# dengenver2_0.net
KiCad netlist of a schematic drawn in EAGLE
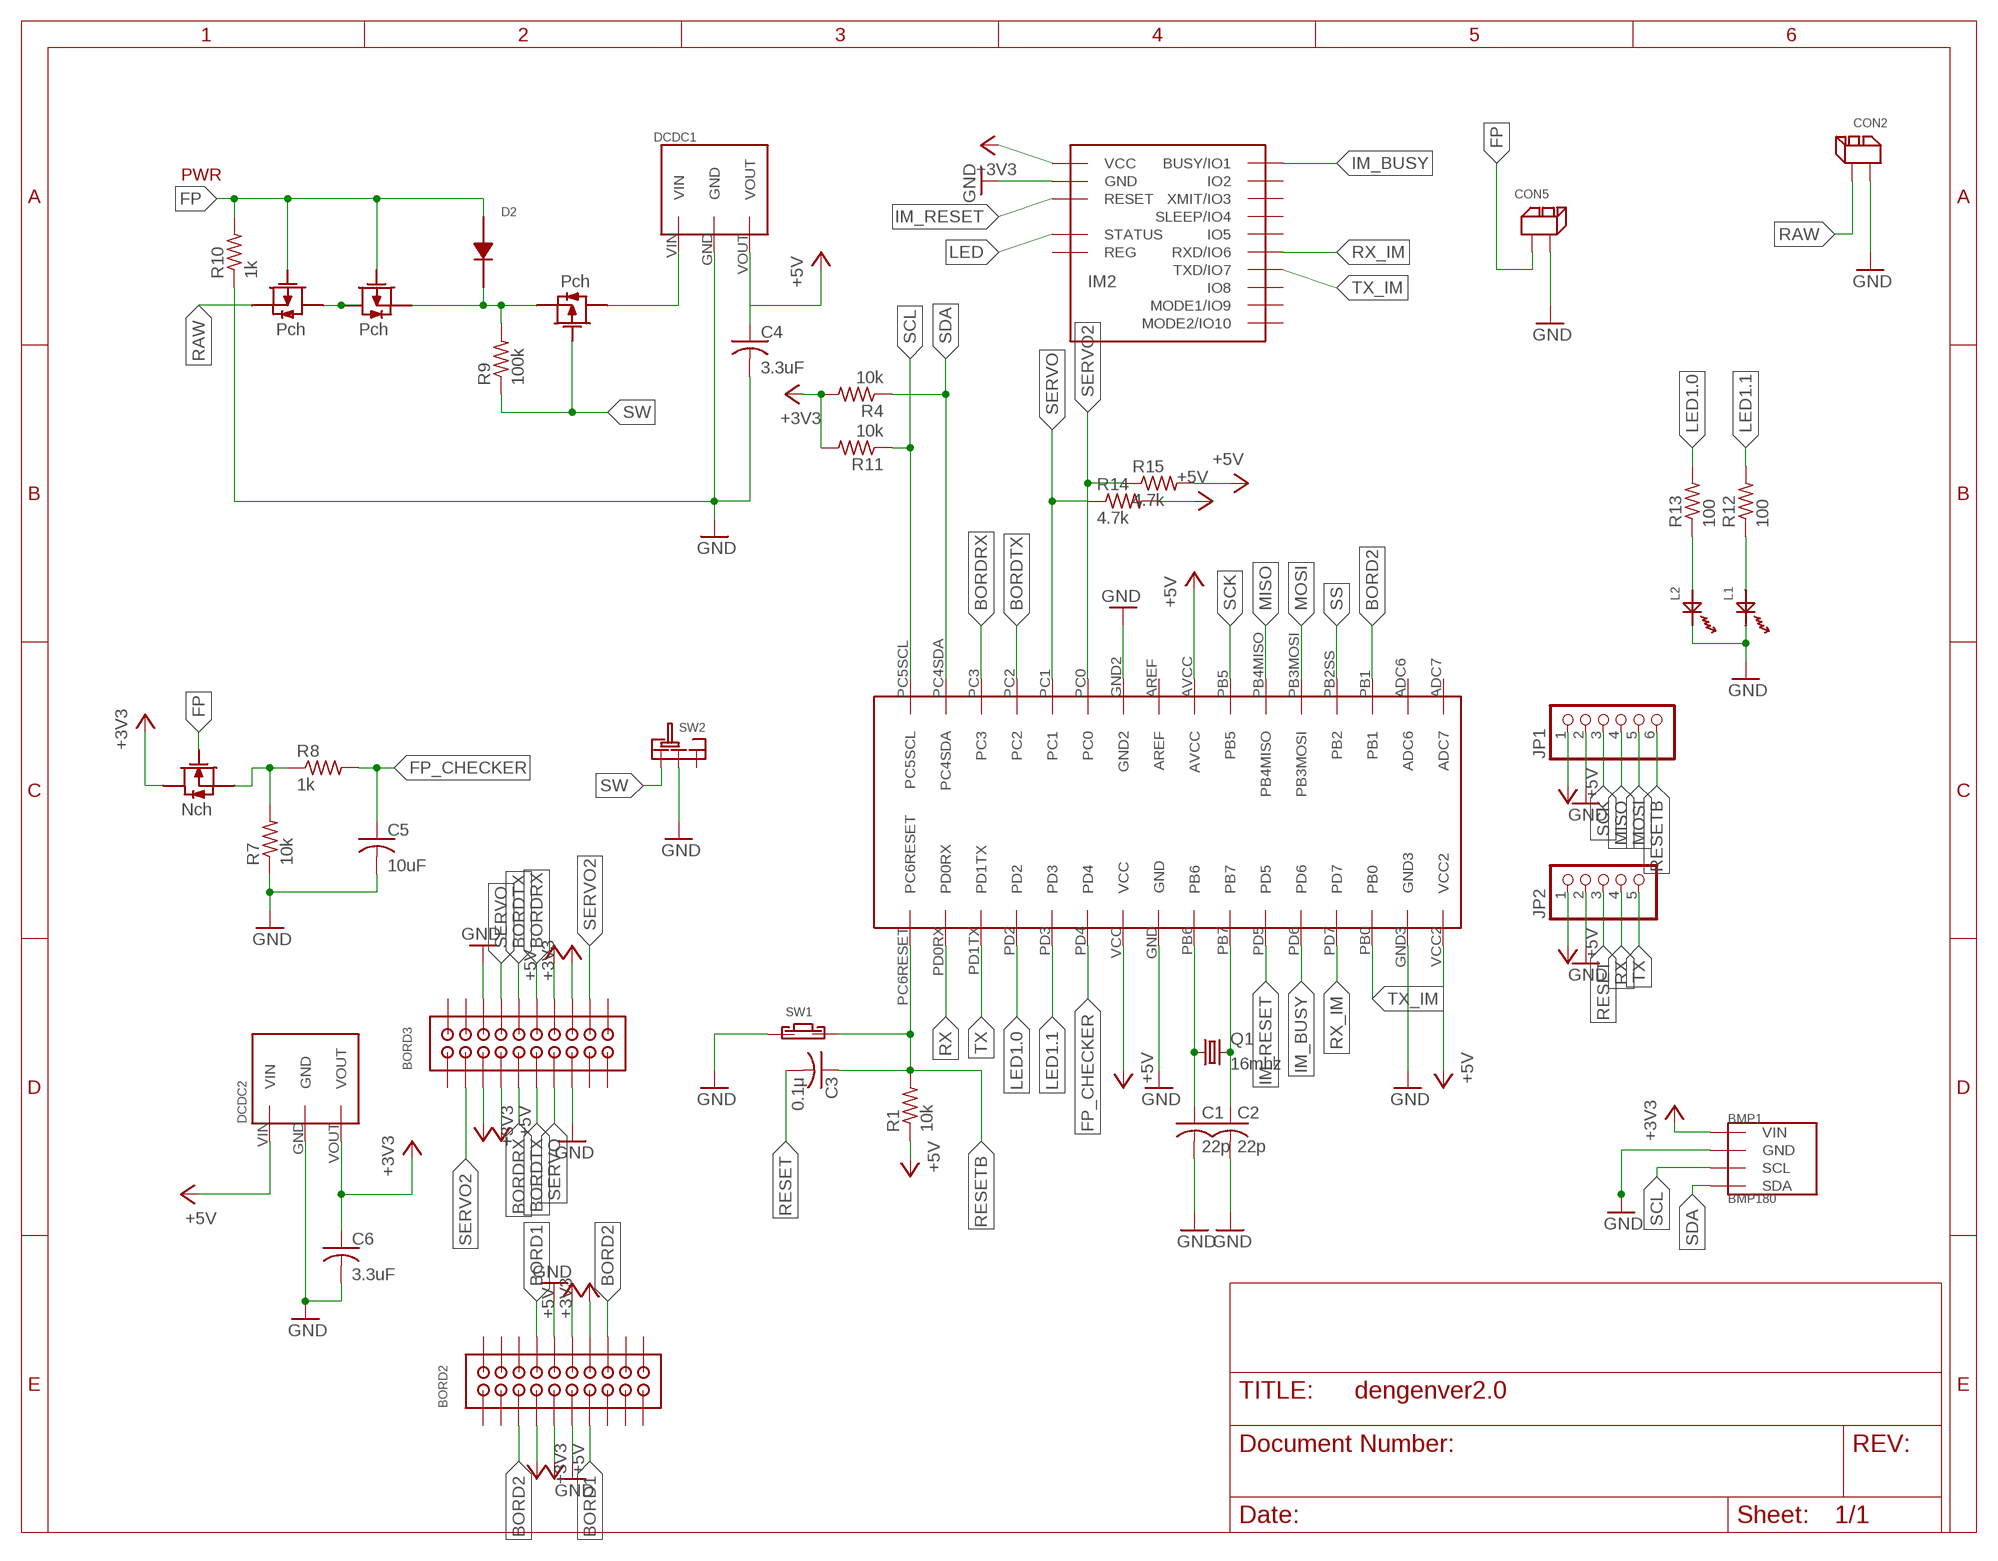
[diagram p0: schematic, sheet 1]

(export (version "E")
  (design (tool "Eeschema 10.0.6"))
  (components
    (comp (ref "BMP1")
      (value "BMP180")
      (footprint "eagle-import:GY-68")
      (libsource (lib "eagle-import") (part "BMP180"))
    )
    (comp (ref "BORD2")
      (value "2X10")
      (footprint "eagle-import:2X10")
      (libsource (lib "eagle-import") (part "2X10"))
    )
    (comp (ref "BORD3")
      (value "2X10")
      (footprint "eagle-import:2X10")
      (libsource (lib "eagle-import") (part "2X10"))
    )
    (comp (ref "C1")
      (value "22p")
      (footprint "eagle-import:C1608")
      (libsource (lib "eagle-import") (part "C-USC1608"))
    )
    (comp (ref "C2")
      (value "22p")
      (footprint "eagle-import:C1608")
      (libsource (lib "eagle-import") (part "C-USC1608"))
    )
    (comp (ref "C3")
      (value "0.1μ")
      (footprint "eagle-import:C1608")
      (libsource (lib "eagle-import") (part "C-USC1608"))
    )
    (comp (ref "C4")
      (value "3.3uF")
      (footprint "eagle-import:C1608")
      (libsource (lib "eagle-import") (part "C-USC1608"))
    )
    (comp (ref "C5")
      (value "10uF")
      (footprint "eagle-import:C1608")
      (libsource (lib "eagle-import") (part "C-USC1608"))
    )
    (comp (ref "C6")
      (value "3.3uF")
      (footprint "eagle-import:C1608")
      (libsource (lib "eagle-import") (part "C-USC1608"))
    )
    (comp (ref "CON2")
      (value "2PIN")
      (footprint "eagle-import:2PIN")
      (libsource (lib "eagle-import") (part "2PIN"))
    )
    (comp (ref "CON5")
      (value "2PIN")
      (footprint "eagle-import:2PIN")
      (libsource (lib "eagle-import") (part "2PIN"))
    )
    (comp (ref "D2")
      (value "1W4148W")
      (footprint "eagle-import:SOD-123")
      (libsource (lib "eagle-import") (part "1W4148W"))
    )
    (comp (ref "DCDC1")
      (value "5V1A_M78AR05-1")
      (footprint "eagle-import:5V1A_M78AR05-1")
      (libsource (lib "eagle-import") (part "5V1A_M78AR05-1"))
    )
    (comp (ref "DCDC2")
      (value "3.3V1A_M78AR033-1")
      (footprint "eagle-import:3.3V1A_M78AR033-1")
      (libsource (lib "eagle-import") (part "3.3V1A_M78AR033-1"))
    )
    (comp (ref "IM2")
      (value "IM920_IM920C")
      (footprint "eagle-import:IM920_IM920C")
      (libsource (lib "eagle-import") (part "IM920_IM920C"))
    )
    (comp (ref "JP1")
      (value "PINHD-1X6")
      (footprint "eagle-import:1X06")
      (libsource (lib "eagle-import") (part "PINHD-1X6"))
    )
    (comp (ref "JP2")
      (value "PINHD-1X5")
      (footprint "eagle-import:1X05")
      (libsource (lib "eagle-import") (part "PINHD-1X5"))
    )
    (comp (ref "L1")
      (value "OSXX1608C1A")
      (footprint "eagle-import:OSXX1608C1A")
      (libsource (lib "eagle-import") (part "OSXX1608C1A"))
    )
    (comp (ref "L2")
      (value "OSXX1608C1A")
      (footprint "eagle-import:OSXX1608C1A")
      (libsource (lib "eagle-import") (part "OSXX1608C1A"))
    )
    (comp (ref "Q1")
      (value "16mhz")
      (footprint "eagle-import:HC49UP")
      (libsource (lib "eagle-import") (part "CRYSTALHC49UP"))
    )
    (comp (ref "R1")
      (value "10k")
      (footprint "eagle-import:R0603")
      (libsource (lib "eagle-import") (part "R-US_R0603"))
    )
    (comp (ref "R4")
      (value "10k")
      (footprint "eagle-import:R0603")
      (libsource (lib "eagle-import") (part "R-US_R0603"))
    )
    (comp (ref "R7")
      (value "10k")
      (footprint "eagle-import:R0603")
      (libsource (lib "eagle-import") (part "R-US_R0603"))
    )
    (comp (ref "R8")
      (value "1k")
      (footprint "eagle-import:R0603")
      (libsource (lib "eagle-import") (part "R-US_R0603"))
    )
    (comp (ref "R9")
      (value "100k")
      (footprint "eagle-import:R0603")
      (libsource (lib "eagle-import") (part "R-US_R0603"))
    )
    (comp (ref "R10")
      (value "1k")
      (footprint "eagle-import:R0603")
      (libsource (lib "eagle-import") (part "R-US_R0603"))
    )
    (comp (ref "R11")
      (value "10k")
      (footprint "eagle-import:R0603")
      (libsource (lib "eagle-import") (part "R-US_R0603"))
    )
    (comp (ref "R12")
      (value "100")
      (footprint "eagle-import:R0603")
      (libsource (lib "eagle-import") (part "R-US_R0603"))
    )
    (comp (ref "R13")
      (value "100")
      (footprint "eagle-import:R0603")
      (libsource (lib "eagle-import") (part "R-US_R0603"))
    )
    (comp (ref "R14")
      (value "4.7k")
      (footprint "eagle-import:R0603")
      (libsource (lib "eagle-import") (part "R-US_R0603"))
    )
    (comp (ref "R15")
      (value "4.7k")
      (footprint "eagle-import:R0603")
      (libsource (lib "eagle-import") (part "R-US_R0603"))
    )
    (comp (ref "SW1")
      (value "TVAF06-A020B-R")
      (footprint "eagle-import:TVAF06-A020B-R")
      (libsource (lib "eagle-import") (part "TVAF06-A020B-R"))
    )
    (comp (ref "SW2")
      (value "SRIDE_SWITCH")
      (footprint "eagle-import:SRIDE_SWITCH")
      (libsource (lib "eagle-import") (part "SRIDE_SWITCH"))
    )
    (comp (ref "U$1")
      (value "ATMEGA328P-AU")
      (footprint "eagle-import:QFP80P900X900X120-32N")
      (libsource (lib "eagle-import") (part "ATMEGA328P-AU"))
    )
    (comp (ref "U$2")
      (value "2SJ681-PCH")
      (footprint "eagle-import:2SJ681")
      (libsource (lib "eagle-import") (part "2SJ681-PCH"))
    )
    (comp (ref "U$3")
      (value "2SK4017-NCH")
      (footprint "eagle-import:2SK4017")
      (libsource (lib "eagle-import") (part "2SK4017-NCH"))
    )
    (comp (ref "U$4")
      (value "2SJ681-PCH")
      (footprint "eagle-import:2SJ681")
      (libsource (lib "eagle-import") (part "2SJ681-PCH"))
    )
    (comp (ref "U$5")
      (value "2SJ681-PCH")
      (footprint "eagle-import:2SJ681")
      (libsource (lib "eagle-import") (part "2SJ681-PCH"))
    )
  )
  (nets
    (net (code "1") (name "+3V3") (class "Default")
      (node (ref "BMP1") (pin "P1") (pinfunction "VIN_P1") (pintype "bidirectional"))
      (node (ref "BORD2") (pin "P$14") (pinfunction "P$14_P$14") (pintype "bidirectional"))
      (node (ref "BORD2") (pin "P$7") (pinfunction "P$7_P$7") (pintype "bidirectional"))
      (node (ref "BORD3") (pin "P$16") (pinfunction "P$16_P$16") (pintype "bidirectional"))
      (node (ref "BORD3") (pin "P$5") (pinfunction "P$5_P$5") (pintype "bidirectional"))
      (node (ref "C6") (pin "1") (pinfunction "1_1") (pintype "passive"))
      (node (ref "DCDC2") (pin "VOUT") (pinfunction "VOUT_VOUT") (pintype "bidirectional"))
      (node (ref "IM2") (pin "$P17") (pinfunction "VCC_$P17") (pintype "bidirectional"))
      (node (ref "R11") (pin "2") (pinfunction "2_2") (pintype "passive"))
      (node (ref "R4") (pin "2") (pinfunction "2_2") (pintype "passive"))
      (node (ref "U$3") (pin "DRAIN") (pinfunction "DRAIN_DRAIN") (pintype "bidirectional"))
    )
    (net (code "2") (name "+5V") (class "Default")
      (node (ref "BORD2") (pin "P$12") (pinfunction "P$12_P$12") (pintype "bidirectional"))
      (node (ref "BORD2") (pin "P$9") (pinfunction "P$9_P$9") (pintype "bidirectional"))
      (node (ref "BORD3") (pin "P$14") (pinfunction "P$14_P$14") (pintype "bidirectional"))
      (node (ref "BORD3") (pin "P$7") (pinfunction "P$7_P$7") (pintype "bidirectional"))
      (node (ref "C4") (pin "1") (pinfunction "1_1") (pintype "passive"))
      (node (ref "DCDC1") (pin "VOUT") (pinfunction "VOUT_VOUT") (pintype "bidirectional"))
      (node (ref "DCDC2") (pin "VIN") (pinfunction "VIN_VIN") (pintype "bidirectional"))
      (node (ref "JP1") (pin "1") (pinfunction "1_1") (pintype "passive"))
      (node (ref "JP2") (pin "1") (pinfunction "1_1") (pintype "passive"))
      (node (ref "R1") (pin "1") (pinfunction "1_1") (pintype "passive"))
      (node (ref "R14") (pin "2") (pinfunction "2_2") (pintype "passive"))
      (node (ref "R15") (pin "2") (pinfunction "2_2") (pintype "passive"))
      (node (ref "U$1") (pin "AVCC") (pinfunction "AVCC_AVCC") (pintype "bidirectional"))
      (node (ref "U$1") (pin "VCC") (pinfunction "VCC_VCC") (pintype "bidirectional"))
      (node (ref "U$1") (pin "VCC2") (pinfunction "VCC2_VCC2") (pintype "bidirectional"))
    )
    (net (code "3") (name "BORD1") (class "Default")
      (node (ref "BORD2") (pin "P$13") (pinfunction "P$13_P$13") (pintype "bidirectional"))
      (node (ref "BORD2") (pin "P$8") (pinfunction "P$8_P$8") (pintype "bidirectional"))
    )
    (net (code "4") (name "BORD2") (class "Default")
      (node (ref "BORD2") (pin "P$16") (pinfunction "P$16_P$16") (pintype "bidirectional"))
      (node (ref "BORD2") (pin "P$5") (pinfunction "P$5_P$5") (pintype "bidirectional"))
      (node (ref "U$1") (pin "PB1") (pinfunction "PB1_PB1") (pintype "bidirectional"))
    )
    (net (code "5") (name "BORDRX") (class "Default")
      (node (ref "BORD3") (pin "P$12") (pinfunction "P$12_P$12") (pintype "bidirectional"))
      (node (ref "BORD3") (pin "P$9") (pinfunction "P$9_P$9") (pintype "bidirectional"))
      (node (ref "U$1") (pin "PC3") (pinfunction "PC3_PC3") (pintype "bidirectional"))
    )
    (net (code "6") (name "BORDTX") (class "Default")
      (node (ref "BORD3") (pin "P$10") (pinfunction "P$10_P$10") (pintype "bidirectional"))
      (node (ref "BORD3") (pin "P$11") (pinfunction "P$11_P$11") (pintype "bidirectional"))
      (node (ref "U$1") (pin "PC2") (pinfunction "PC2_PC2") (pintype "bidirectional"))
    )
    (net (code "7") (name "FP") (class "Default")
      (node (ref "CON5") (pin "P$1") (pinfunction "P$1_P$1") (pintype "bidirectional"))
      (node (ref "D2") (pin "C") (pinfunction "C_C") (pintype "bidirectional"))
      (node (ref "R10") (pin "2") (pinfunction "2_2") (pintype "passive"))
      (node (ref "U$2") (pin "GATE") (pinfunction "GATE_GATE") (pintype "bidirectional"))
      (node (ref "U$3") (pin "GATE") (pinfunction "GATE_GATE") (pintype "bidirectional"))
      (node (ref "U$4") (pin "GATE") (pinfunction "GATE_GATE") (pintype "bidirectional"))
    )
    (net (code "8") (name "FP_CHECKER") (class "Default")
      (node (ref "C5") (pin "1") (pinfunction "1_1") (pintype "passive"))
      (node (ref "R8") (pin "2") (pinfunction "2_2") (pintype "passive"))
      (node (ref "U$1") (pin "PD4") (pinfunction "PD4_PD4") (pintype "bidirectional"))
    )
    (net (code "9") (name "GND") (class "Default")
      (node (ref "BMP1") (pin "P2") (pinfunction "GND_P2") (pintype "bidirectional"))
      (node (ref "BORD2") (pin "P$10") (pinfunction "P$10_P$10") (pintype "bidirectional"))
      (node (ref "BORD2") (pin "P$11") (pinfunction "P$11_P$11") (pintype "bidirectional"))
      (node (ref "BORD3") (pin "P$15") (pinfunction "P$15_P$15") (pintype "bidirectional"))
      (node (ref "BORD3") (pin "P$6") (pinfunction "P$6_P$6") (pintype "bidirectional"))
      (node (ref "C1") (pin "2") (pinfunction "2_2") (pintype "passive"))
      (node (ref "C2") (pin "2") (pinfunction "2_2") (pintype "passive"))
      (node (ref "C4") (pin "2") (pinfunction "2_2") (pintype "passive"))
      (node (ref "C5") (pin "2") (pinfunction "2_2") (pintype "passive"))
      (node (ref "C6") (pin "2") (pinfunction "2_2") (pintype "passive"))
      (node (ref "CON2") (pin "P$1") (pinfunction "P$1_P$1") (pintype "bidirectional"))
      (node (ref "CON5") (pin "P$2") (pinfunction "P$2_P$2") (pintype "bidirectional"))
      (node (ref "DCDC1") (pin "GND") (pinfunction "GND_GND") (pintype "bidirectional"))
      (node (ref "DCDC2") (pin "GND") (pinfunction "GND_GND") (pintype "bidirectional"))
      (node (ref "IM2") (pin "$P18") (pinfunction "GND_$P18") (pintype "bidirectional"))
      (node (ref "JP1") (pin "2") (pinfunction "2_2") (pintype "passive"))
      (node (ref "JP2") (pin "2") (pinfunction "2_2") (pintype "passive"))
      (node (ref "L1") (pin "CT") (pinfunction "CT_CT") (pintype "bidirectional"))
      (node (ref "L2") (pin "CT") (pinfunction "CT_CT") (pintype "bidirectional"))
      (node (ref "R10") (pin "1") (pinfunction "1_1") (pintype "passive"))
      (node (ref "R7") (pin "1") (pinfunction "1_1") (pintype "passive"))
      (node (ref "SW1") (pin "P$1") (pinfunction "P$1_P$1") (pintype "bidirectional"))
      (node (ref "SW2") (pin "LR") (pinfunction "LR_LR") (pintype "bidirectional"))
      (node (ref "U$1") (pin "GND") (pinfunction "GND_GND") (pintype "bidirectional"))
      (node (ref "U$1") (pin "GND2") (pinfunction "GND2_GND2") (pintype "bidirectional"))
      (node (ref "U$1") (pin "GND3") (pinfunction "GND3_GND3") (pintype "bidirectional"))
    )
    (net (code "10") (name "IM_BUSY") (class "Default")
      (node (ref "IM2") (pin "$P1") (pinfunction "BUSY/IO1_$P1") (pintype "bidirectional"))
      (node (ref "U$1") (pin "PD6") (pinfunction "PD6_PD6") (pintype "bidirectional"))
    )
    (net (code "11") (name "IM_RESET") (class "Default")
      (node (ref "IM2") (pin "$P19") (pinfunction "RESET_$P19") (pintype "bidirectional"))
      (node (ref "U$1") (pin "PD5") (pinfunction "PD5_PD5") (pintype "bidirectional"))
    )
    (net (code "12") (name "LED") (class "Default")
      (node (ref "IM2") (pin "$P15") (pinfunction "STATUS_$P15") (pintype "bidirectional"))
    )
    (net (code "13") (name "LED1.0") (class "Default")
      (node (ref "R13") (pin "2") (pinfunction "2_2") (pintype "passive"))
      (node (ref "U$1") (pin "PD2") (pinfunction "PD2_PD2") (pintype "bidirectional"))
    )
    (net (code "14") (name "LED1.1") (class "Default")
      (node (ref "R12") (pin "2") (pinfunction "2_2") (pintype "passive"))
      (node (ref "U$1") (pin "PD3") (pinfunction "PD3_PD3") (pintype "bidirectional"))
    )
    (net (code "15") (name "MISO") (class "Default")
      (node (ref "JP1") (pin "4") (pinfunction "4_4") (pintype "passive"))
      (node (ref "U$1") (pin "PB4MISO") (pinfunction "PB4MISO_PB4MISO") (pintype "bidirectional"))
    )
    (net (code "16") (name "MOSI") (class "Default")
      (node (ref "JP1") (pin "5") (pinfunction "5_5") (pintype "passive"))
      (node (ref "U$1") (pin "PB3MOSI") (pinfunction "PB3MOSI_PB3MOSI") (pintype "bidirectional"))
    )
    (net (code "17") (name "Net-(C1-Pad1)") (class "Default")
      (node (ref "C1") (pin "1") (pinfunction "1_1") (pintype "passive"))
      (node (ref "Q1") (pin "1") (pinfunction "1_1") (pintype "passive"))
      (node (ref "U$1") (pin "PB6") (pinfunction "PB6_PB6") (pintype "bidirectional"))
    )
    (net (code "18") (name "Net-(C2-Pad1)") (class "Default")
      (node (ref "C2") (pin "1") (pinfunction "1_1") (pintype "passive"))
      (node (ref "Q1") (pin "2") (pinfunction "2_2") (pintype "passive"))
      (node (ref "U$1") (pin "PB7") (pinfunction "PB7_PB7") (pintype "bidirectional"))
    )
    (net (code "19") (name "Net-(D2-PadA)") (class "Default")
      (node (ref "D2") (pin "A") (pinfunction "A_A") (pintype "bidirectional"))
      (node (ref "R9") (pin "2") (pinfunction "2_2") (pintype "passive"))
      (node (ref "U$4") (pin "SOURCE") (pinfunction "SOURCE_SOURCE") (pintype "bidirectional"))
      (node (ref "U$5") (pin "SOURCE") (pinfunction "SOURCE_SOURCE") (pintype "bidirectional"))
    )
    (net (code "20") (name "Net-(DCDC1-PadVIN)") (class "Default")
      (node (ref "DCDC1") (pin "VIN") (pinfunction "VIN_VIN") (pintype "bidirectional"))
      (node (ref "U$5") (pin "DRAIN") (pinfunction "DRAIN_DRAIN") (pintype "bidirectional"))
    )
    (net (code "21") (name "Net-(L1-PadAN)") (class "Default")
      (node (ref "L1") (pin "AN") (pinfunction "AN_AN") (pintype "bidirectional"))
      (node (ref "R12") (pin "1") (pinfunction "1_1") (pintype "passive"))
    )
    (net (code "22") (name "Net-(L2-PadAN)") (class "Default")
      (node (ref "L2") (pin "AN") (pinfunction "AN_AN") (pintype "bidirectional"))
      (node (ref "R13") (pin "1") (pinfunction "1_1") (pintype "passive"))
    )
    (net (code "23") (name "Net-(R7-Pad2)") (class "Default")
      (node (ref "R7") (pin "2") (pinfunction "2_2") (pintype "passive"))
      (node (ref "R8") (pin "1") (pinfunction "1_1") (pintype "passive"))
      (node (ref "U$3") (pin "SOURCE") (pinfunction "SOURCE_SOURCE") (pintype "bidirectional"))
    )
    (net (code "24") (name "Net-(U$2-PadDRAIN)") (class "Default")
      (node (ref "U$2") (pin "DRAIN") (pinfunction "DRAIN_DRAIN") (pintype "bidirectional"))
      (node (ref "U$4") (pin "DRAIN") (pinfunction "DRAIN_DRAIN") (pintype "bidirectional"))
    )
    (net (code "25") (name "RAW") (class "Default")
      (node (ref "CON2") (pin "P$2") (pinfunction "P$2_P$2") (pintype "bidirectional"))
      (node (ref "U$2") (pin "SOURCE") (pinfunction "SOURCE_SOURCE") (pintype "bidirectional"))
    )
    (net (code "26") (name "RESET") (class "Default")
      (node (ref "C3") (pin "2") (pinfunction "2_2") (pintype "passive"))
      (node (ref "JP2") (pin "3") (pinfunction "3_3") (pintype "passive"))
    )
    (net (code "27") (name "RESETB") (class "Default")
      (node (ref "C3") (pin "1") (pinfunction "1_1") (pintype "passive"))
      (node (ref "JP1") (pin "6") (pinfunction "6_6") (pintype "passive"))
      (node (ref "R1") (pin "2") (pinfunction "2_2") (pintype "passive"))
      (node (ref "SW1") (pin "P$2") (pinfunction "P$2_P$2") (pintype "bidirectional"))
      (node (ref "U$1") (pin "PC6RESET") (pinfunction "PC6RESET_PC6RESET") (pintype "bidirectional"))
    )
    (net (code "28") (name "RX") (class "Default")
      (node (ref "JP2") (pin "4") (pinfunction "4_4") (pintype "passive"))
      (node (ref "U$1") (pin "PD0RX") (pinfunction "PD0RX_PD0RX") (pintype "bidirectional"))
    )
    (net (code "29") (name "RX_IM") (class "Default")
      (node (ref "IM2") (pin "$P6") (pinfunction "RXD/IO6_$P6") (pintype "bidirectional"))
      (node (ref "U$1") (pin "PD7") (pinfunction "PD7_PD7") (pintype "bidirectional"))
    )
    (net (code "30") (name "SCK") (class "Default")
      (node (ref "JP1") (pin "3") (pinfunction "3_3") (pintype "passive"))
      (node (ref "U$1") (pin "PB5") (pinfunction "PB5_PB5") (pintype "bidirectional"))
    )
    (net (code "31") (name "SCL") (class "Default")
      (node (ref "BMP1") (pin "P3") (pinfunction "SCL_P3") (pintype "bidirectional"))
      (node (ref "R11") (pin "1") (pinfunction "1_1") (pintype "passive"))
      (node (ref "U$1") (pin "PC5SCL") (pinfunction "PC5SCL_PC5SCL") (pintype "bidirectional"))
    )
    (net (code "32") (name "SDA") (class "Default")
      (node (ref "BMP1") (pin "P4") (pinfunction "SDA_P4") (pintype "bidirectional"))
      (node (ref "R4") (pin "1") (pinfunction "1_1") (pintype "passive"))
      (node (ref "U$1") (pin "PC4SDA") (pinfunction "PC4SDA_PC4SDA") (pintype "bidirectional"))
    )
    (net (code "33") (name "SERVO") (class "Default")
      (node (ref "BORD3") (pin "P$13") (pinfunction "P$13_P$13") (pintype "bidirectional"))
      (node (ref "BORD3") (pin "P$8") (pinfunction "P$8_P$8") (pintype "bidirectional"))
      (node (ref "R14") (pin "1") (pinfunction "1_1") (pintype "passive"))
      (node (ref "U$1") (pin "PC1") (pinfunction "PC1_PC1") (pintype "bidirectional"))
    )
    (net (code "34") (name "SERVO2") (class "Default")
      (node (ref "BORD3") (pin "P$18") (pinfunction "P$18_P$18") (pintype "bidirectional"))
      (node (ref "BORD3") (pin "P$3") (pinfunction "P$3_P$3") (pintype "bidirectional"))
      (node (ref "R15") (pin "1") (pinfunction "1_1") (pintype "passive"))
      (node (ref "U$1") (pin "PC0") (pinfunction "PC0_PC0") (pintype "bidirectional"))
    )
    (net (code "35") (name "SS") (class "Default")
      (node (ref "U$1") (pin "PB2SS") (pinfunction "PB2_PB2SS") (pintype "bidirectional"))
    )
    (net (code "36") (name "SW") (class "Default")
      (node (ref "R9") (pin "1") (pinfunction "1_1") (pintype "passive"))
      (node (ref "SW2") (pin "L") (pinfunction "L_L") (pintype "bidirectional"))
      (node (ref "U$5") (pin "GATE") (pinfunction "GATE_GATE") (pintype "bidirectional"))
    )
    (net (code "37") (name "TX") (class "Default")
      (node (ref "JP2") (pin "5") (pinfunction "5_5") (pintype "passive"))
      (node (ref "U$1") (pin "PD1TX") (pinfunction "PD1TX_PD1TX") (pintype "bidirectional"))
    )
    (net (code "38") (name "TX_IM") (class "Default")
      (node (ref "IM2") (pin "$P7") (pinfunction "TXD/IO7_$P7") (pintype "bidirectional"))
      (node (ref "U$1") (pin "PB0") (pinfunction "PB0_PB0") (pintype "bidirectional"))
    )
    (net (code "39") (name "unconnected-(BORD2-PadP$1)") (class "Default")
      (node (ref "BORD2") (pin "P$1") (pinfunction "P$1_P$1") (pintype "bidirectional"))
    )
    (net (code "40") (name "unconnected-(BORD2-PadP$2)") (class "Default")
      (node (ref "BORD2") (pin "P$2") (pinfunction "P$2_P$2") (pintype "bidirectional"))
    )
    (net (code "41") (name "unconnected-(BORD2-PadP$3)") (class "Default")
      (node (ref "BORD2") (pin "P$3") (pinfunction "P$3_P$3") (pintype "bidirectional"))
    )
    (net (code "42") (name "unconnected-(BORD2-PadP$4)") (class "Default")
      (node (ref "BORD2") (pin "P$4") (pinfunction "P$4_P$4") (pintype "bidirectional"))
    )
    (net (code "43") (name "unconnected-(BORD2-PadP$6)") (class "Default")
      (node (ref "BORD2") (pin "P$6") (pinfunction "P$6_P$6") (pintype "bidirectional"))
    )
    (net (code "44") (name "unconnected-(BORD2-PadP$15)") (class "Default")
      (node (ref "BORD2") (pin "P$15") (pinfunction "P$15_P$15") (pintype "bidirectional"))
    )
    (net (code "45") (name "unconnected-(BORD2-PadP$17)") (class "Default")
      (node (ref "BORD2") (pin "P$17") (pinfunction "P$17_P$17") (pintype "bidirectional"))
    )
    (net (code "46") (name "unconnected-(BORD2-PadP$18)") (class "Default")
      (node (ref "BORD2") (pin "P$18") (pinfunction "P$18_P$18") (pintype "bidirectional"))
    )
    (net (code "47") (name "unconnected-(BORD2-PadP$19)") (class "Default")
      (node (ref "BORD2") (pin "P$19") (pinfunction "P$19_P$19") (pintype "bidirectional"))
    )
    (net (code "48") (name "unconnected-(BORD2-PadP$20)") (class "Default")
      (node (ref "BORD2") (pin "P$20") (pinfunction "P$20_P$20") (pintype "bidirectional"))
    )
    (net (code "49") (name "unconnected-(BORD3-PadP$1)") (class "Default")
      (node (ref "BORD3") (pin "P$1") (pinfunction "P$1_P$1") (pintype "bidirectional"))
    )
    (net (code "50") (name "unconnected-(BORD3-PadP$2)") (class "Default")
      (node (ref "BORD3") (pin "P$2") (pinfunction "P$2_P$2") (pintype "bidirectional"))
    )
    (net (code "51") (name "unconnected-(BORD3-PadP$4)") (class "Default")
      (node (ref "BORD3") (pin "P$4") (pinfunction "P$4_P$4") (pintype "bidirectional"))
    )
    (net (code "52") (name "unconnected-(BORD3-PadP$17)") (class "Default")
      (node (ref "BORD3") (pin "P$17") (pinfunction "P$17_P$17") (pintype "bidirectional"))
    )
    (net (code "53") (name "unconnected-(BORD3-PadP$19)") (class "Default")
      (node (ref "BORD3") (pin "P$19") (pinfunction "P$19_P$19") (pintype "bidirectional"))
    )
    (net (code "54") (name "unconnected-(BORD3-PadP$20)") (class "Default")
      (node (ref "BORD3") (pin "P$20") (pinfunction "P$20_P$20") (pintype "bidirectional"))
    )
    (net (code "55") (name "unconnected-(IM2-IO2-Pad$P2)") (class "Default")
      (node (ref "IM2") (pin "$P2") (pinfunction "IO2_$P2") (pintype "bidirectional"))
    )
    (net (code "56") (name "unconnected-(IM2-IO5-Pad$P5)") (class "Default")
      (node (ref "IM2") (pin "$P5") (pinfunction "IO5_$P5") (pintype "bidirectional"))
    )
    (net (code "57") (name "unconnected-(IM2-IO8-Pad$P8)") (class "Default")
      (node (ref "IM2") (pin "$P8") (pinfunction "IO8_$P8") (pintype "bidirectional"))
    )
    (net (code "58") (name "unconnected-(IM2-MODE1{slash}IO9-Pad$P9)") (class "Default")
      (node (ref "IM2") (pin "$P9") (pinfunction "MODE1/IO9_$P9") (pintype "bidirectional"))
    )
    (net (code "59") (name "unconnected-(IM2-MODE2{slash}IO10-Pad$P10)") (class "Default")
      (node (ref "IM2") (pin "$P10") (pinfunction "MODE2/IO10_$P10") (pintype "bidirectional"))
    )
    (net (code "60") (name "unconnected-(IM2-REG-Pad$P16)") (class "Default")
      (node (ref "IM2") (pin "$P16") (pinfunction "REG_$P16") (pintype "bidirectional"))
    )
    (net (code "61") (name "unconnected-(IM2-SLEEP{slash}IO4-Pad$P4)") (class "Default")
      (node (ref "IM2") (pin "$P4") (pinfunction "SLEEP/IO4_$P4") (pintype "bidirectional"))
    )
    (net (code "62") (name "unconnected-(IM2-XMIT{slash}IO3-Pad$P3)") (class "Default")
      (node (ref "IM2") (pin "$P3") (pinfunction "XMIT/IO3_$P3") (pintype "bidirectional"))
    )
    (net (code "63") (name "unconnected-(SW2-PadR)") (class "Default")
      (node (ref "SW2") (pin "R") (pinfunction "R_R") (pintype "bidirectional"))
    )
    (net (code "64") (name "unconnected-(U$1-PadADC6)") (class "Default")
      (node (ref "U$1") (pin "ADC6") (pinfunction "ADC6_ADC6") (pintype "bidirectional"))
    )
    (net (code "65") (name "unconnected-(U$1-PadADC7)") (class "Default")
      (node (ref "U$1") (pin "ADC7") (pinfunction "ADC7_ADC7") (pintype "bidirectional"))
    )
    (net (code "66") (name "unconnected-(U$1-PadAREF)") (class "Default")
      (node (ref "U$1") (pin "AREF") (pinfunction "AREF_AREF") (pintype "bidirectional"))
    )
  )
)
